# SCH_joystick_board_2025-02-11.net
KiCad netlist of a schematic drawn in EasyEDA
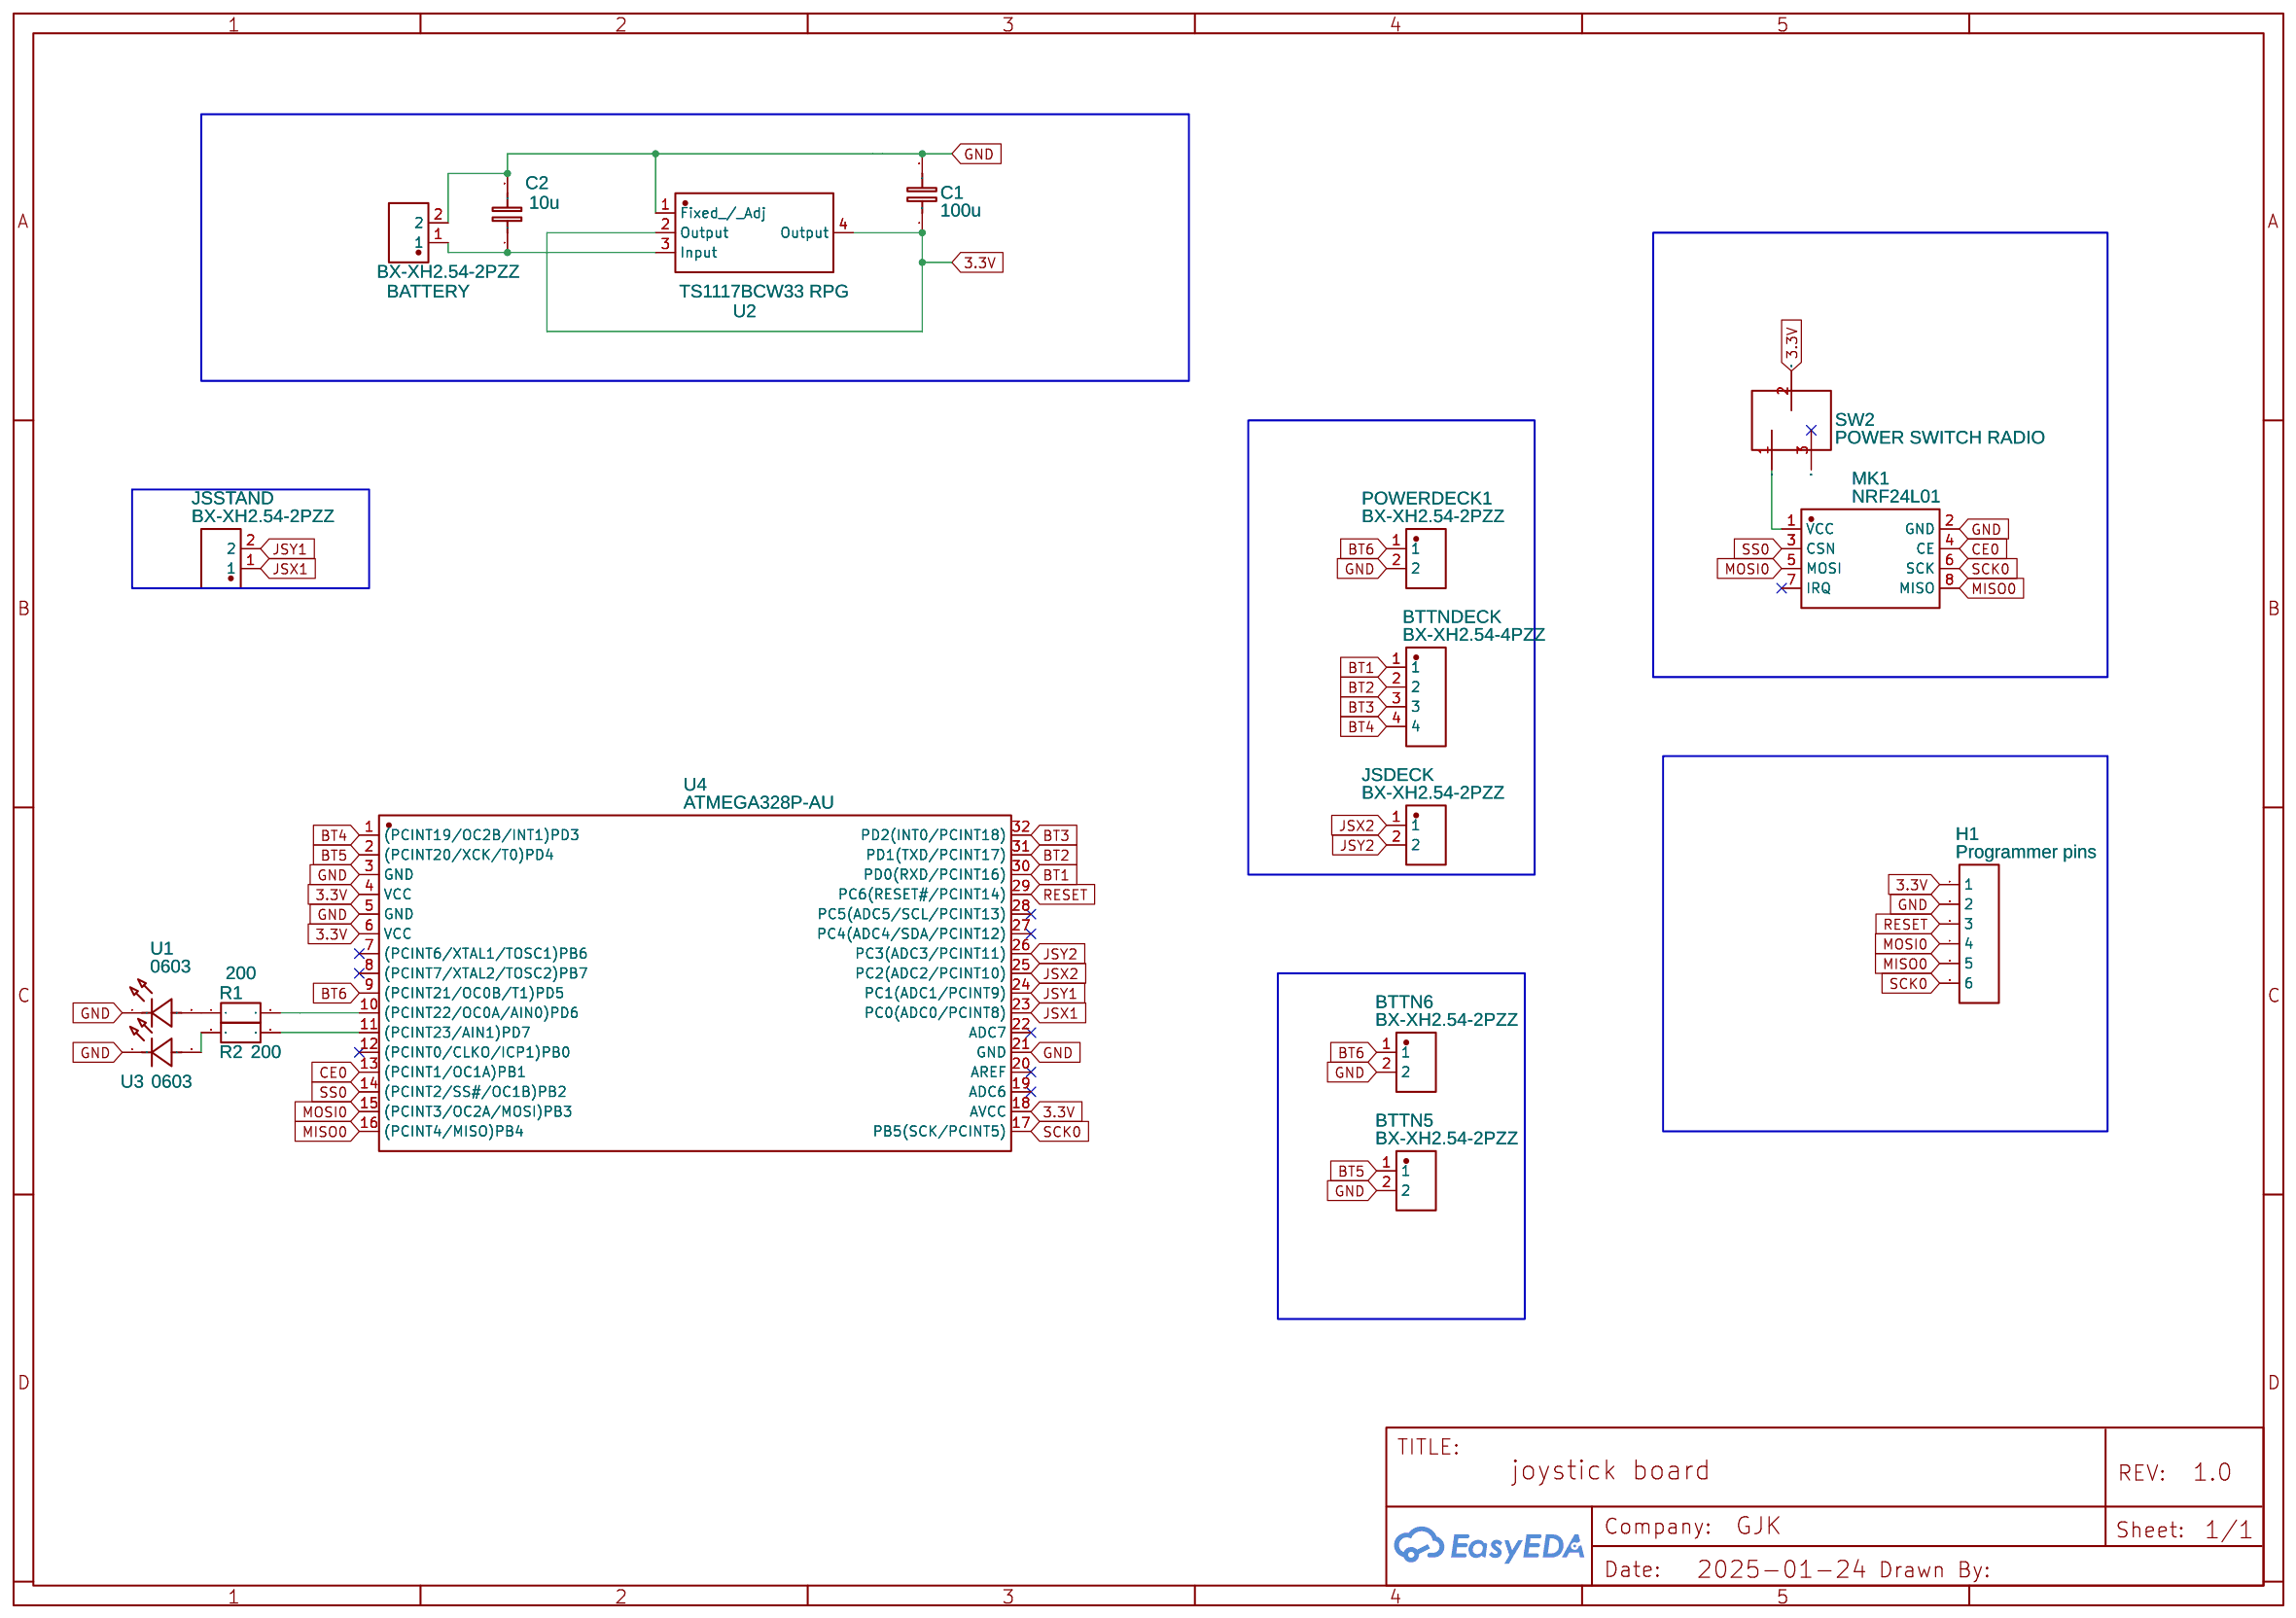
[diagram p0: schematic sheet]

(export (version "E")
  (design (tool "Eeschema 10.0.6"))
  (components
    (comp (ref "BATTERY")
      (value "BX-XH2.54-2PZZ")
      (fields (field (name "Manufacturer") "Bossie(博锡)"))
      (libsource (lib "") (part "BX-XH2.54-2PZZ"))
    )
    (comp (ref "BTTN5")
      (value "BX-XH2.54-2PZZ")
      (fields (field (name "Manufacturer") "Bossie(博锡)"))
      (libsource (lib "") (part "BX-XH2.54-2PZZ_4"))
    )
    (comp (ref "BTTN6")
      (value "BX-XH2.54-2PZZ")
      (fields (field (name "Manufacturer") "Bossie(博锡)"))
      (libsource (lib "") (part "BX-XH2.54-2PZZ_4"))
    )
    (comp (ref "BTTNDECK")
      (value "BX-XH2.54-4PZZ")
      (fields (field (name "Manufacturer") "Bossie(博锡)"))
      (libsource (lib "") (part "BX-XH2.54-4PZZ"))
    )
    (comp (ref "C1") (value "100u") (libsource (lib "") (part "C_0603_EU")))
    (comp (ref "C2") (value "10u") (libsource (lib "") (part "C_0603_EU")))
    (comp (ref "H1")
      (value "Programmer pins")
      (fields (field (name "Manufacturer Part") "2.54-1x6P直针") (field (name "Manufacturer") "BOOMELE(博穆精密)"))
      (libsource (lib "") (part "Header-Male-2.54_1x6"))
    )
    (comp (ref "JSDECK")
      (value "BX-XH2.54-2PZZ")
      (fields (field (name "Manufacturer") "Bossie(博锡)"))
      (libsource (lib "") (part "BX-XH2.54-2PZZ_3"))
    )
    (comp (ref "JSSTAND")
      (value "BX-XH2.54-2PZZ")
      (fields (field (name "Manufacturer") "Bossie(博锡)"))
      (libsource (lib "") (part "BX-XH2.54-2PZZ_1"))
    )
    (comp (ref "MK1")
      (value "NRF24L01")
      (fields (field (name "Manufacturer Part") "NF-04") (field (name "Manufacturer") "Ai-Thinker(安信可)"))
      (libsource (lib "") (part "NRF24L01"))
    )
    (comp (ref "POWERDECK1")
      (value "BX-XH2.54-2PZZ")
      (fields (field (name "Manufacturer") "Bossie(博锡)"))
      (libsource (lib "") (part "BX-XH2.54-2PZZ_2"))
    )
    (comp (ref "R1") (value "200") (libsource (lib "") (part "R_0603_EU")))
    (comp (ref "R2") (value "200") (libsource (lib "") (part "R_0603_EU")))
    (comp (ref "SW2")
      (value "POWER SWITCH RADIO")
      (fields
        (field (name "Manufacturer Part") "DIP switch 8bit,Dip Switch,DSWB03LHGET")
        (field (name "Manufacturer") "KE")
      )
      (libsource (lib "") (part "DIP_SWITCH 3PIN COPY"))
    )
    (comp (ref "U1") (value "0603") (libsource (lib "") (part "0603")))
    (comp (ref "U2")
      (value "TS1117BCW33 RPG")
      (fields (field (name "Manufacturer") "Taiwan Semiconductor(台湾半导体)"))
      (libsource (lib "") (part "TS1117BCW33 RPG"))
    )
    (comp (ref "U3") (value "0603") (libsource (lib "") (part "0603")))
    (comp (ref "U4")
      (value "ATMEGA328P-AU")
      (fields (field (name "Manufacturer") "MICROCHIP(美国微芯)"))
      (libsource (lib "") (part "ATMEGA328P-AU"))
    )
  )
  (nets
    (net (code "1") (name "3.3V") (class "Default")
      (node (ref "C1") (pin "1") (pinfunction "1_1") (pintype "unspecified"))
      (node (ref "H1") (pin "1") (pinfunction "1_1") (pintype "input"))
      (node (ref "SW2") (pin "2") (pinfunction "P2_2") (pintype "unspecified"))
      (node (ref "U2") (pin "2") (pinfunction "Output_2") (pintype "unspecified"))
      (node (ref "U2") (pin "4") (pinfunction "Output_4") (pintype "unspecified"))
      (node (ref "U4") (pin "18") (pinfunction "AVCC_18") (pintype "unspecified"))
      (node (ref "U4") (pin "4") (pinfunction "VCC_4") (pintype "unspecified"))
      (node (ref "U4") (pin "6") (pinfunction "VCC_6") (pintype "unspecified"))
    )
    (net (code "2") (name "BT1") (class "Default")
      (node (ref "BTTNDECK") (pin "1") (pinfunction "1_1") (pintype "unspecified"))
      (node (ref "U4") (pin "30") (pinfunction "PD0(RXD/PCINT16)_30") (pintype "unspecified"))
    )
    (net (code "3") (name "BT2") (class "Default")
      (node (ref "BTTNDECK") (pin "2") (pinfunction "2_2") (pintype "unspecified"))
      (node (ref "U4") (pin "31") (pinfunction "PD1(TXD/PCINT17)_31") (pintype "unspecified"))
    )
    (net (code "4") (name "BT3") (class "Default")
      (node (ref "BTTNDECK") (pin "3") (pinfunction "3_3") (pintype "unspecified"))
      (node (ref "U4") (pin "32") (pinfunction "PD2(INT0/PCINT18)_32") (pintype "unspecified"))
    )
    (net (code "5") (name "BT4") (class "Default")
      (node (ref "BTTNDECK") (pin "4") (pinfunction "4_4") (pintype "unspecified"))
      (node (ref "U4") (pin "1") (pinfunction "(PCINT19/OC2B/INT1)PD3_1") (pintype "unspecified"))
    )
    (net (code "6") (name "BT5") (class "Default")
      (node (ref "BTTN5") (pin "1") (pinfunction "1_1") (pintype "unspecified"))
      (node (ref "U4") (pin "2") (pinfunction "(PCINT20/XCK/T0)PD4_2") (pintype "unspecified"))
    )
    (net (code "7") (name "BT6") (class "Default")
      (node (ref "BTTN6") (pin "1") (pinfunction "1_1") (pintype "unspecified"))
      (node (ref "POWERDECK1") (pin "1") (pinfunction "1_1") (pintype "unspecified"))
      (node (ref "U4") (pin "9") (pinfunction "(PCINT21/OC0B/T1)PD5_9") (pintype "unspecified"))
    )
    (net (code "8") (name "CE0") (class "Default")
      (node (ref "MK1") (pin "4") (pinfunction "CE_4") (pintype "unspecified"))
      (node (ref "U4") (pin "13") (pinfunction "(PCINT1/OC1A)PB1_13") (pintype "unspecified"))
    )
    (net (code "9") (name "GND") (class "Default")
      (node (ref "BATTERY") (pin "2") (pinfunction "2_2") (pintype "unspecified"))
      (node (ref "BTTN5") (pin "2") (pinfunction "2_2") (pintype "unspecified"))
      (node (ref "BTTN6") (pin "2") (pinfunction "2_2") (pintype "unspecified"))
      (node (ref "C1") (pin "2") (pinfunction "2_2") (pintype "unspecified"))
      (node (ref "C2") (pin "2") (pinfunction "2_2") (pintype "unspecified"))
      (node (ref "H1") (pin "2") (pinfunction "2_2") (pintype "input"))
      (node (ref "MK1") (pin "2") (pinfunction "GND_2") (pintype "unspecified"))
      (node (ref "POWERDECK1") (pin "2") (pinfunction "2_2") (pintype "unspecified"))
      (node (ref "U1") (pin "1") (pinfunction "K_1") (pintype "unspecified"))
      (node (ref "U2") (pin "1") (pinfunction "Fixed_/_Adj_1") (pintype "unspecified"))
      (node (ref "U3") (pin "1") (pinfunction "K_1") (pintype "unspecified"))
      (node (ref "U4") (pin "21") (pinfunction "GND_21") (pintype "unspecified"))
      (node (ref "U4") (pin "3") (pinfunction "GND_3") (pintype "unspecified"))
      (node (ref "U4") (pin "5") (pinfunction "GND_5") (pintype "unspecified"))
    )
    (net (code "10") (name "JSX1") (class "Default")
      (node (ref "JSSTAND") (pin "1") (pinfunction "1_1") (pintype "unspecified"))
      (node (ref "U4") (pin "23") (pinfunction "PC0(ADC0/PCINT8)_23") (pintype "unspecified"))
    )
    (net (code "11") (name "JSX2") (class "Default")
      (node (ref "JSDECK") (pin "1") (pinfunction "1_1") (pintype "unspecified"))
      (node (ref "U4") (pin "25") (pinfunction "PC2(ADC2/PCINT10)_25") (pintype "unspecified"))
    )
    (net (code "12") (name "JSY1") (class "Default")
      (node (ref "JSSTAND") (pin "2") (pinfunction "2_2") (pintype "unspecified"))
      (node (ref "U4") (pin "24") (pinfunction "PC1(ADC1/PCINT9)_24") (pintype "unspecified"))
    )
    (net (code "13") (name "JSY2") (class "Default")
      (node (ref "JSDECK") (pin "2") (pinfunction "2_2") (pintype "unspecified"))
      (node (ref "U4") (pin "26") (pinfunction "PC3(ADC3/PCINT11)_26") (pintype "unspecified"))
    )
    (net (code "14") (name "MISO0") (class "Default")
      (node (ref "H1") (pin "5") (pinfunction "5_5") (pintype "input"))
      (node (ref "MK1") (pin "8") (pinfunction "MISO_8") (pintype "unspecified"))
      (node (ref "U4") (pin "16") (pinfunction "(PCINT4/MISO)PB4_16") (pintype "unspecified"))
    )
    (net (code "15") (name "MOSI0") (class "Default")
      (node (ref "H1") (pin "4") (pinfunction "4_4") (pintype "input"))
      (node (ref "MK1") (pin "5") (pinfunction "MOSI_5") (pintype "unspecified"))
      (node (ref "U4") (pin "15") (pinfunction "(PCINT3/OC2A/MOSI)PB3_15") (pintype "unspecified"))
    )
    (net (code "16") (name "Net-(MK1-VCC)") (class "Default")
      (node (ref "MK1") (pin "1") (pinfunction "VCC_1") (pintype "unspecified"))
      (node (ref "SW2") (pin "1") (pinfunction "P1_1") (pintype "unspecified"))
    )
    (net (code "17") (name "Net-(U1-A)") (class "Default")
      (node (ref "R1") (pin "1") (pinfunction "1_1") (pintype "unspecified"))
      (node (ref "U1") (pin "2") (pinfunction "A_2") (pintype "unspecified"))
    )
    (net (code "18") (name "Net-(U2-Input)") (class "Default")
      (node (ref "BATTERY") (pin "1") (pinfunction "1_1") (pintype "unspecified"))
      (node (ref "C2") (pin "1") (pinfunction "1_1") (pintype "unspecified"))
      (node (ref "U2") (pin "3") (pinfunction "Input_3") (pintype "unspecified"))
    )
    (net (code "19") (name "Net-(U3-A)") (class "Default")
      (node (ref "R2") (pin "1") (pinfunction "1_1") (pintype "unspecified"))
      (node (ref "U3") (pin "2") (pinfunction "A_2") (pintype "unspecified"))
    )
    (net (code "20") (name "Net-(U4-(PCINT22{slash}OC0A{slash}AIN0)PD6)") (class "Default")
      (node (ref "R1") (pin "2") (pinfunction "2_2") (pintype "unspecified"))
      (node (ref "U4") (pin "10") (pinfunction "(PCINT22/OC0A/AIN0)PD6_10") (pintype "unspecified"))
    )
    (net (code "21") (name "Net-(U4-(PCINT23{slash}AIN1)PD7)") (class "Default")
      (node (ref "R2") (pin "2") (pinfunction "2_2") (pintype "unspecified"))
      (node (ref "U4") (pin "11") (pinfunction "(PCINT23/AIN1)PD7_11") (pintype "unspecified"))
    )
    (net (code "22") (name "RESET") (class "Default")
      (node (ref "H1") (pin "3") (pinfunction "3_3") (pintype "input"))
      (node (ref "U4") (pin "29") (pinfunction "PC6(RESET#/PCINT14)_29") (pintype "unspecified"))
    )
    (net (code "23") (name "SCK0") (class "Default")
      (node (ref "H1") (pin "6") (pinfunction "6_6") (pintype "input"))
      (node (ref "MK1") (pin "6") (pinfunction "SCK_6") (pintype "unspecified"))
      (node (ref "U4") (pin "17") (pinfunction "PB5(SCK/PCINT5)_17") (pintype "unspecified"))
    )
    (net (code "24") (name "SS0") (class "Default")
      (node (ref "MK1") (pin "3") (pinfunction "CSN_3") (pintype "unspecified"))
      (node (ref "U4") (pin "14") (pinfunction "(PCINT2/SS#/OC1B)PB2_14") (pintype "unspecified"))
    )
    (net (code "25") (name "unconnected-(MK1-IRQ-Pad7)") (class "Default")
      (node (ref "MK1") (pin "7") (pinfunction "IRQ_7") (pintype "unspecified+no_connect"))
    )
    (net (code "26") (name "unconnected-(SW2-P3-Pad3)") (class "Default")
      (node (ref "SW2") (pin "3") (pinfunction "P3_3") (pintype "unspecified+no_connect"))
    )
    (net (code "27") (name "unconnected-(U4-(PCINT0{slash}CLKO{slash}ICP1)PB0-Pad12)") (class "Default")
      (node (ref "U4") (pin "12") (pinfunction "(PCINT0/CLKO/ICP1)PB0_12") (pintype "unspecified+no_connect"))
    )
    (net (code "28") (name "unconnected-(U4-(PCINT6{slash}XTAL1{slash}TOSC1)PB6-Pad7)") (class "Default")
      (node (ref "U4") (pin "7") (pinfunction "(PCINT6/XTAL1/TOSC1)PB6_7") (pintype "unspecified+no_connect"))
    )
    (net (code "29") (name "unconnected-(U4-(PCINT7{slash}XTAL2{slash}TOSC2)PB7-Pad8)") (class "Default")
      (node (ref "U4") (pin "8") (pinfunction "(PCINT7/XTAL2/TOSC2)PB7_8") (pintype "unspecified+no_connect"))
    )
    (net (code "30") (name "unconnected-(U4-ADC6-Pad19)") (class "Default")
      (node (ref "U4") (pin "19") (pinfunction "ADC6_19") (pintype "unspecified+no_connect"))
    )
    (net (code "31") (name "unconnected-(U4-ADC7-Pad22)") (class "Default")
      (node (ref "U4") (pin "22") (pinfunction "ADC7_22") (pintype "unspecified+no_connect"))
    )
    (net (code "32") (name "unconnected-(U4-AREF-Pad20)") (class "Default")
      (node (ref "U4") (pin "20") (pinfunction "AREF_20") (pintype "unspecified+no_connect"))
    )
    (net (code "33") (name "unconnected-(U4-PC4(ADC4{slash}SDA{slash}PCINT12)-Pad27)") (class "Default")
      (node (ref "U4") (pin "27") (pinfunction "PC4(ADC4/SDA/PCINT12)_27") (pintype "unspecified+no_connect"))
    )
    (net (code "34") (name "unconnected-(U4-PC5(ADC5{slash}SCL{slash}PCINT13)-Pad28)") (class "Default")
      (node (ref "U4") (pin "28") (pinfunction "PC5(ADC5/SCL/PCINT13)_28") (pintype "unspecified+no_connect"))
    )
  )
)
